# 555-test.net
KiCad netlist of a schematic drawn in EAGLE
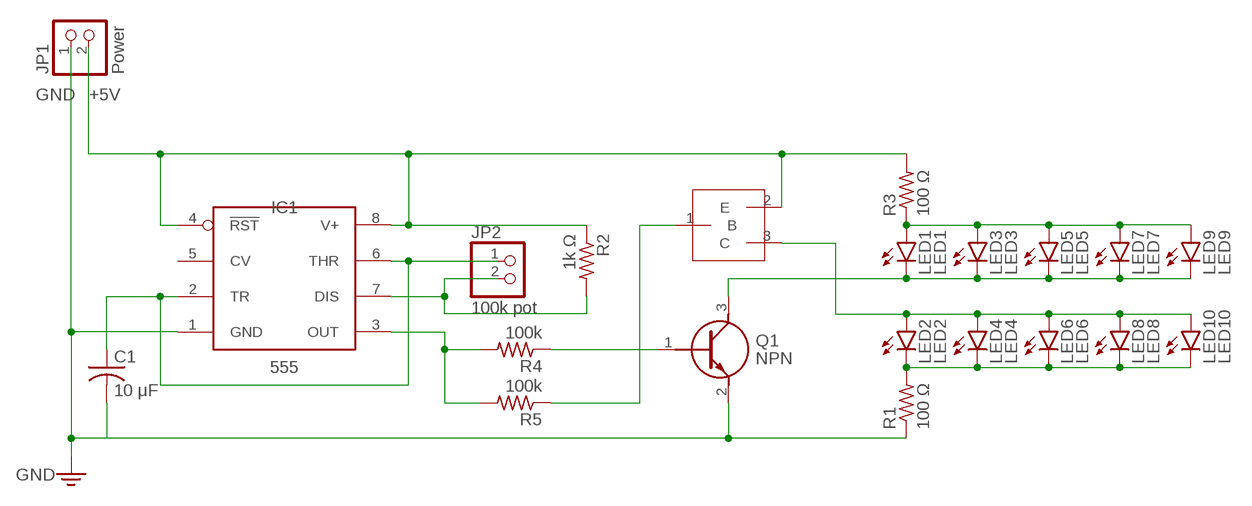
[diagram p0: schematic, sheet 1]

(export (version "E")
  (design (tool "Eeschema 10.0.6"))
  (components
    (comp (ref "C1")
      (value "10 μF")
      (footprint "eagle-import:CAPC2012X110")
      (libsource (lib "eagle-import") (part "C-USCHIP-0805(2012-METRIC)_"))
    )
    (comp (ref "IC1")
      (value "555")
      (footprint "eagle-import:SOIC127P599X175-8N")
      (fields (field (name "MANUFACTURER") "Texas Instruments ") (field (name "MPN") "NE555D "))
      (libsource (lib "eagle-import") (part "555_SOICNE"))
    )
    (comp (ref "JP1")
      (value "Power")
      (footprint "eagle-import:1X02")
      (libsource (lib "eagle-import") (part "PINHD-1X2"))
    )
    (comp (ref "JP2")
      (value "100k pot")
      (footprint "eagle-import:1X02")
      (libsource (lib "eagle-import") (part "PINHD-1X2"))
    )
    (comp (ref "LED1")
      (value "LED1")
      (footprint "eagle-import:CHIP-LED0805")
      (libsource (lib "eagle-import") (part "LEDCHIP-LED0805"))
    )
    (comp (ref "LED2")
      (value "LED2")
      (footprint "eagle-import:CHIP-LED0805")
      (libsource (lib "eagle-import") (part "LEDCHIP-LED0805"))
    )
    (comp (ref "LED3")
      (value "LED3")
      (footprint "eagle-import:CHIP-LED0805")
      (libsource (lib "eagle-import") (part "LEDCHIP-LED0805"))
    )
    (comp (ref "LED4")
      (value "LED4")
      (footprint "eagle-import:CHIP-LED0805")
      (libsource (lib "eagle-import") (part "LEDCHIP-LED0805"))
    )
    (comp (ref "LED5")
      (value "LED5")
      (footprint "eagle-import:CHIP-LED0805")
      (libsource (lib "eagle-import") (part "LEDCHIP-LED0805"))
    )
    (comp (ref "LED6")
      (value "LED6")
      (footprint "eagle-import:CHIP-LED0805")
      (libsource (lib "eagle-import") (part "LEDCHIP-LED0805"))
    )
    (comp (ref "LED7")
      (value "LED7")
      (footprint "eagle-import:CHIP-LED0805")
      (libsource (lib "eagle-import") (part "LEDCHIP-LED0805"))
    )
    (comp (ref "LED8")
      (value "LED8")
      (footprint "eagle-import:CHIP-LED0805")
      (libsource (lib "eagle-import") (part "LEDCHIP-LED0805"))
    )
    (comp (ref "LED9")
      (value "LED9")
      (footprint "eagle-import:CHIP-LED0805")
      (libsource (lib "eagle-import") (part "LEDCHIP-LED0805"))
    )
    (comp (ref "LED10")
      (value "LED10")
      (footprint "eagle-import:CHIP-LED0805")
      (libsource (lib "eagle-import") (part "LEDCHIP-LED0805"))
    )
    (comp (ref "Q1")
      (value "NPN")
      (footprint "eagle-import:PMBT2222A215")
      (fields
        (field (name "MANUFACTURER_PART_NUMBER") "PMBT2222A,215")
        (field (name "MOUSER_PART_NUMBER") "771-PMBT2222A-T/R")
      )
      (libsource (lib "eagle-import") (part "PMBT2222A,215"))
    )
    (comp (ref "R1")
      (value "100 Ω")
      (footprint "eagle-import:M0805")
      (libsource (lib "eagle-import") (part "R-US_M0805"))
    )
    (comp (ref "R2")
      (value "1k Ω")
      (footprint "eagle-import:M0805")
      (libsource (lib "eagle-import") (part "R-US_M0805"))
    )
    (comp (ref "R3")
      (value "100 Ω")
      (footprint "eagle-import:M0805")
      (libsource (lib "eagle-import") (part "R-US_M0805"))
    )
    (comp (ref "R4")
      (value "100k")
      (footprint "eagle-import:M0805")
      (libsource (lib "eagle-import") (part "R-US_M0805"))
    )
    (comp (ref "R5")
      (value "100k")
      (footprint "eagle-import:M0805")
      (libsource (lib "eagle-import") (part "R-US_M0805"))
    )
    (comp (ref "U$1")
      (value "PNP")
      (footprint "eagle-import:SOT95P230X110-3N")
      (libsource (lib "eagle-import") (part "2PB709ARL,235"))
    )
  )
  (nets
    (net (code "1") (name "/+5V") (class "Default")
      (node (ref "IC1") (pin "4") (pinfunction "~{RST}_4") (pintype "input"))
      (node (ref "IC1") (pin "8") (pinfunction "V+_8") (pintype "power_in"))
      (node (ref "JP1") (pin "2") (pinfunction "2_2") (pintype "passive"))
      (node (ref "R2") (pin "1") (pinfunction "1_1") (pintype "passive"))
      (node (ref "R3") (pin "2") (pinfunction "2_2") (pintype "passive"))
      (node (ref "U$1") (pin "2") (pinfunction "E_2") (pintype "bidirectional"))
    )
    (net (code "2") (name "GND") (class "Default")
      (node (ref "C1") (pin "2") (pinfunction "2_2") (pintype "passive"))
      (node (ref "IC1") (pin "1") (pinfunction "GND_1") (pintype "power_in"))
      (node (ref "JP1") (pin "1") (pinfunction "1_1") (pintype "passive"))
      (node (ref "Q1") (pin "2") (pinfunction "E_2") (pintype "bidirectional"))
      (node (ref "R1") (pin "1") (pinfunction "1_1") (pintype "passive"))
    )
    (net (code "3") (name "Net-(IC1-DIS)") (class "Default")
      (node (ref "IC1") (pin "7") (pinfunction "DIS_7") (pintype "input"))
      (node (ref "JP2") (pin "2") (pinfunction "2_2") (pintype "passive"))
      (node (ref "R2") (pin "2") (pinfunction "2_2") (pintype "passive"))
    )
    (net (code "4") (name "Net-(IC1-OUT)") (class "Default")
      (node (ref "IC1") (pin "3") (pinfunction "OUT_3") (pintype "output"))
      (node (ref "R4") (pin "2") (pinfunction "2_2") (pintype "passive"))
      (node (ref "R5") (pin "2") (pinfunction "2_2") (pintype "passive"))
    )
    (net (code "5") (name "Net-(IC1-THR)") (class "Default")
      (node (ref "C1") (pin "1") (pinfunction "1_1") (pintype "passive"))
      (node (ref "IC1") (pin "2") (pinfunction "TR_2") (pintype "input"))
      (node (ref "IC1") (pin "6") (pinfunction "THR_6") (pintype "input"))
      (node (ref "JP2") (pin "1") (pinfunction "1_1") (pintype "passive"))
    )
    (net (code "6") (name "Net-(LED1-PadA)") (class "Default")
      (node (ref "LED1") (pin "A") (pinfunction "A_A") (pintype "passive"))
      (node (ref "LED3") (pin "A") (pinfunction "A_A") (pintype "passive"))
      (node (ref "LED5") (pin "A") (pinfunction "A_A") (pintype "passive"))
      (node (ref "LED7") (pin "A") (pinfunction "A_A") (pintype "passive"))
      (node (ref "LED9") (pin "A") (pinfunction "A_A") (pintype "passive"))
      (node (ref "R3") (pin "1") (pinfunction "1_1") (pintype "passive"))
    )
    (net (code "7") (name "Net-(LED10-PadC)") (class "Default")
      (node (ref "LED10") (pin "C") (pinfunction "C_C") (pintype "passive"))
      (node (ref "LED2") (pin "C") (pinfunction "C_C") (pintype "passive"))
      (node (ref "LED4") (pin "C") (pinfunction "C_C") (pintype "passive"))
      (node (ref "LED6") (pin "C") (pinfunction "C_C") (pintype "passive"))
      (node (ref "LED8") (pin "C") (pinfunction "C_C") (pintype "passive"))
      (node (ref "R1") (pin "2") (pinfunction "2_2") (pintype "passive"))
    )
    (net (code "8") (name "Net-(Q1-B)") (class "Default")
      (node (ref "Q1") (pin "1") (pinfunction "B_1") (pintype "bidirectional"))
      (node (ref "R4") (pin "1") (pinfunction "1_1") (pintype "passive"))
    )
    (net (code "9") (name "Net-(Q1-C)") (class "Default")
      (node (ref "LED1") (pin "C") (pinfunction "C_C") (pintype "passive"))
      (node (ref "LED3") (pin "C") (pinfunction "C_C") (pintype "passive"))
      (node (ref "LED5") (pin "C") (pinfunction "C_C") (pintype "passive"))
      (node (ref "LED7") (pin "C") (pinfunction "C_C") (pintype "passive"))
      (node (ref "LED9") (pin "C") (pinfunction "C_C") (pintype "passive"))
      (node (ref "Q1") (pin "3") (pinfunction "C_3") (pintype "bidirectional"))
    )
    (net (code "10") (name "Net-(U$1-B)") (class "Default")
      (node (ref "R5") (pin "1") (pinfunction "1_1") (pintype "passive"))
      (node (ref "U$1") (pin "1") (pinfunction "B_1") (pintype "bidirectional"))
    )
    (net (code "11") (name "Net-(U$1-C)") (class "Default")
      (node (ref "LED10") (pin "A") (pinfunction "A_A") (pintype "passive"))
      (node (ref "LED2") (pin "A") (pinfunction "A_A") (pintype "passive"))
      (node (ref "LED4") (pin "A") (pinfunction "A_A") (pintype "passive"))
      (node (ref "LED6") (pin "A") (pinfunction "A_A") (pintype "passive"))
      (node (ref "LED8") (pin "A") (pinfunction "A_A") (pintype "passive"))
      (node (ref "U$1") (pin "3") (pinfunction "C_3") (pintype "bidirectional"))
    )
    (net (code "12") (name "unconnected-(IC1-CV-Pad5)") (class "Default")
      (node (ref "IC1") (pin "5") (pinfunction "CV_5") (pintype "input"))
    )
  )
)
